# SSFocuser-A-DRV8825.net
KiCad netlist of a schematic drawn in Altium Designer
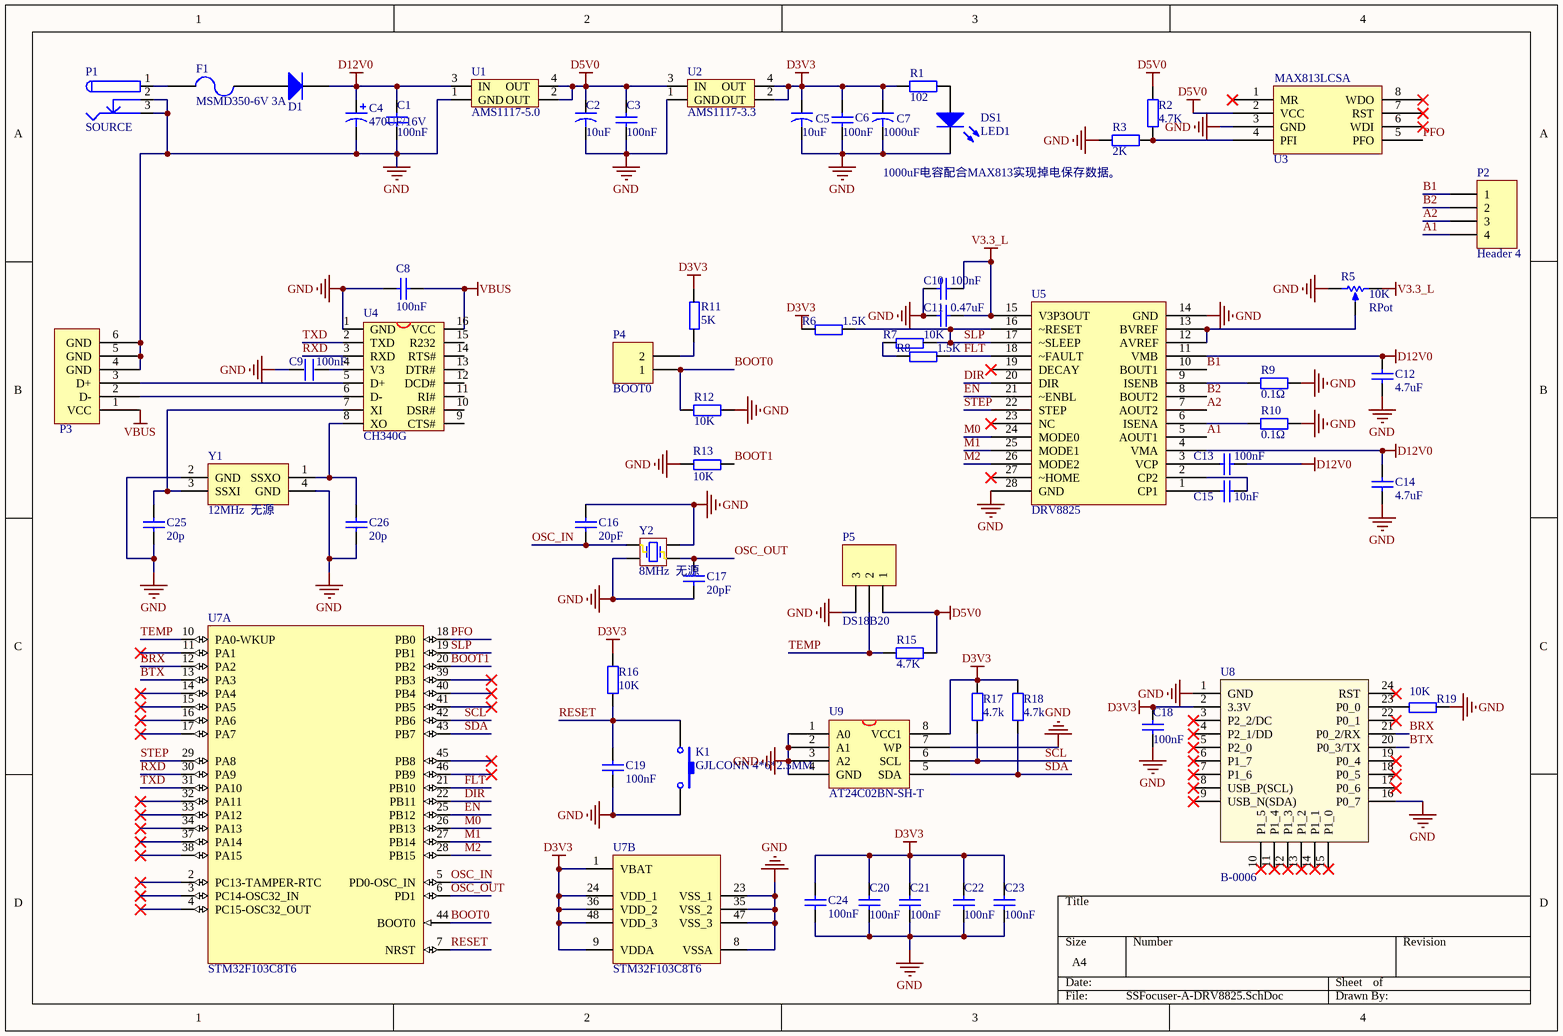
[diagram p0: SSFocuser-A-DRV8825.SchDoc]

(export (version "E")
  (design (tool "Eeschema 10.0.6"))
  (components
    (comp (ref "C1")
      (value "100nF")
      (footprint "0603C")
      (description "Capacitor")
      (fields (field (name "PUBLISHER") "Altium Limited"))
      (libsource (lib "Crazy_PCB") (part "Cap"))
    )
    (comp (ref "C2")
      (value "10uF")
      (footprint "3216")
      (fields (field (name "VAULE") "10uF"))
      (libsource (lib "Crazy_PCB") (part "CAP2"))
    )
    (comp (ref "C3")
      (value "100nF")
      (footprint "0603C")
      (description "Capacitor")
      (fields (field (name "PUBLISHER") "Altium Limited"))
      (libsource (lib "Crazy_PCB") (part "Cap"))
    )
    (comp (ref "C4")
      (value "470UF/16V")
      (footprint "16V/470U(CD10X10D5)")
      (description "470UF      16V      CD10X10D5")
      (libsource (lib "平台原理图symbol图库V1.0") (part "C470UF016S"))
    )
    (comp (ref "C5")
      (value "10uF")
      (footprint "3216")
      (fields (field (name "VAULE") "10uF"))
      (libsource (lib "Crazy_PCB") (part "CAP2"))
    )
    (comp (ref "C6")
      (value "100nF")
      (footprint "0603C")
      (description "Capacitor")
      (fields (field (name "PUBLISHER") "Altium Limited"))
      (libsource (lib "Crazy_PCB") (part "Cap"))
    )
    (comp (ref "C7")
      (value "1000uF")
      (footprint "16V/470U(CD10X10D5)")
      (fields (field (name "VAULE") "1000uF"))
      (libsource (lib "Crazy_PCB") (part "CAP2"))
    )
    (comp (ref "C8")
      (value "100nF")
      (footprint "0603C")
      (description "Capacitor")
      (fields (field (name "PUBLISHER") "Altium Limited"))
      (libsource (lib "Crazy_PCB") (part "Cap"))
    )
    (comp (ref "C9")
      (value "100nF")
      (footprint "0603C")
      (libsource (lib "WarShip V3 STM32103封装库") (part "C"))
    )
    (comp (ref "C10")
      (value "100nF")
      (footprint "0603C")
      (description "Capacitor")
      (fields (field (name "PUBLISHER") "Altium Limited"))
      (libsource (lib "Crazy_PCB") (part "Cap"))
    )
    (comp (ref "C11")
      (value "0.47uF")
      (footprint "0603C")
      (description "Capacitor")
      (fields (field (name "PUBLISHER") "Altium Limited"))
      (libsource (lib "Crazy_PCB") (part "Cap"))
    )
    (comp (ref "C12")
      (value "4.7uF")
      (footprint "1206C")
      (description "Capacitor")
      (fields (field (name "PUBLISHER") "Altium Limited"))
      (libsource (lib "Crazy_PCB") (part "Cap"))
    )
    (comp (ref "C13")
      (value "100nF")
      (footprint "0603C")
      (description "Capacitor")
      (fields (field (name "PUBLISHER") "Altium Limited"))
      (libsource (lib "Crazy_PCB") (part "Cap"))
    )
    (comp (ref "C14")
      (value "4.7uF")
      (footprint "1206C")
      (description "Capacitor")
      (fields (field (name "PUBLISHER") "Altium Limited"))
      (libsource (lib "Crazy_PCB") (part "Cap"))
    )
    (comp (ref "C15")
      (value "10nF")
      (footprint "0603C")
      (description "Capacitor")
      (fields (field (name "PUBLISHER") "Altium Limited"))
      (libsource (lib "Crazy_PCB") (part "Cap"))
    )
    (comp (ref "C16")
      (value "20pF")
      (footprint "0603C")
      (description "Capacitor")
      (fields (field (name "PUBLISHER") "Altium Limited"))
      (libsource (lib "JL_SCH") (part "Cap"))
    )
    (comp (ref "C17")
      (value "20pF")
      (footprint "0603C")
      (description "Capacitor")
      (fields (field (name "PUBLISHER") "Altium Limited"))
      (libsource (lib "JL_SCH") (part "Cap"))
    )
    (comp (ref "C18")
      (value "100nF")
      (footprint "0603C")
      (description "Capacitor")
      (fields (field (name "PUBLISHER") "Altium Limited"))
      (libsource (lib "Crazy_PCB") (part "Cap"))
    )
    (comp (ref "C19")
      (value "100nF")
      (footprint "0603C")
      (description "Capacitor")
      (fields (field (name "PUBLISHER") "Altium Limited"))
      (libsource (lib "Crazy_PCB") (part "Cap"))
    )
    (comp (ref "C20")
      (value "100nF")
      (footprint "0603C")
      (description "Capacitor")
      (fields (field (name "PUBLISHER") "Altium Limited"))
      (libsource (lib "Crazy_PCB") (part "Cap"))
    )
    (comp (ref "C21")
      (value "100nF")
      (footprint "0603C")
      (description "Capacitor")
      (fields (field (name "PUBLISHER") "Altium Limited"))
      (libsource (lib "Crazy_PCB") (part "Cap"))
    )
    (comp (ref "C22")
      (value "100nF")
      (footprint "0603C")
      (description "Capacitor")
      (fields (field (name "PUBLISHER") "Altium Limited"))
      (libsource (lib "Crazy_PCB") (part "Cap"))
    )
    (comp (ref "C23")
      (value "100nF")
      (footprint "0603C")
      (description "Capacitor")
      (fields (field (name "PUBLISHER") "Altium Limited"))
      (libsource (lib "Crazy_PCB") (part "Cap"))
    )
    (comp (ref "C24")
      (value "100nF")
      (footprint "0603C")
      (description "Capacitor")
      (fields (field (name "PUBLISHER") "Altium Limited"))
      (libsource (lib "Crazy_PCB") (part "Cap"))
    )
    (comp (ref "C25")
      (value "20p")
      (footprint "0603C")
      (description "Capacitor")
      (fields (field (name "PUBLISHER") "Altium Limited"))
      (libsource (lib "Crazy_PCB") (part "Cap"))
    )
    (comp (ref "C26")
      (value "20p")
      (footprint "0603C")
      (description "Capacitor")
      (fields (field (name "PUBLISHER") "Altium Limited"))
      (libsource (lib "Crazy_PCB") (part "Cap"))
    )
    (comp (ref "D1")
      (value "M7")
      (footprint "DO-214AC")
      (description "High Conductance Fast Diode")
      (fields (field (name "PUBLISHER") "Altium Limited"))
      (libsource (lib "Crazy_PCB") (part "Diode"))
    )
    (comp (ref "DS1")
      (value "LED1")
      (footprint "0805D")
      (description "Typical RED, GREEN, YELLOW, AMBER GaAs LED")
      (fields (field (name "PUBLISHER") "Altium Limited"))
      (libsource (lib "MiniSTM32 V3.0封装库") (part "LED2"))
    )
    (comp (ref "F1")
      (value "MSMD350-6V 3A")
      (footprint "1812R")
      (description "Fuse")
      (libsource (lib "JL_SCH") (part "FUSE2"))
    )
    (comp (ref "K1")
      (value "GJLCONN 4*6*2.5MM")
      (footprint "SW-4*6")
      (description "Switch")
      (fields (field (name "PUBLISHER") "Altium Limited"))
      (libsource (lib "Crazy_PCB") (part "KEY2"))
    )
    (comp (ref "P1")
      (value "SOURCE")
      (footprint "DC_5.5MM")
      (fields (field (name "PUBLISHER") "Altium Limited"))
      (libsource (lib "Crazy_PCB") (part "SOURCE"))
    )
    (comp (ref "P2")
      (value "Header 4")
      (footprint "XH_4_V")
      (description "Header, 4-Pin")
      (fields (field (name "PUBLISHER") "Altium Limited"))
      (libsource (lib "Miscellaneous Connectors") (part "Header 4"))
    )
    (comp (ref "P3") (value "USB-B") (footprint "USB-B") (libsource (lib "DX") (part "USB-B")))
    (comp (ref "P4")
      (value "BOOT0")
      (footprint "HDR1X2")
      (description "Header, 2-Pin")
      (fields (field (name "PUBLISHER") "Altium Limited"))
      (libsource (lib "Miscellaneous Connectors") (part "MHDR1X2"))
    )
    (comp (ref "P5")
      (value "DS18B20")
      (footprint "TO-92B")
      (description "Header, 3-Pin")
      (fields (field (name "PUBLISHER") "Altium Limited"))
      (libsource (lib "Miscellaneous Connectors") (part "Header 3"))
    )
    (comp (ref "R1")
      (value "102")
      (footprint "0603R")
      (description "Resistor")
      (fields (field (name "PUBLISHER") "Altium Limited"))
      (libsource (lib "") (part "RES_2"))
    )
    (comp (ref "R2")
      (value "4.7K")
      (footprint "0603R")
      (description "Resistor")
      (fields (field (name "PUBLISHER") "Altium Limited"))
      (libsource (lib "") (part "RES_1"))
    )
    (comp (ref "R3")
      (value "2K")
      (footprint "0603R")
      (description "Resistor")
      (fields (field (name "PUBLISHER") "Altium Limited"))
      (libsource (lib "") (part "RES_2"))
    )
    (comp (ref "R5")
      (value "RPot")
      (footprint "VR_SMD")
      (description "Potentiometer")
      (fields (field (name "ALTIUM_VALUE") "10K") (field (name "PUBLISHER") "Altium Limited"))
      (libsource (lib "Miscellaneous Devices") (part "RPot"))
    )
    (comp (ref "R6") (value "1.5K") (footprint "0603R") (libsource (lib "WarShip V3 STM32103封装库") (part "R")))
    (comp (ref "R7") (value "10K") (footprint "0603R") (libsource (lib "WarShip V3 STM32103封装库") (part "R")))
    (comp (ref "R8") (value "1.5K") (footprint "0603R") (libsource (lib "WarShip V3 STM32103封装库") (part "R")))
    (comp (ref "R9")
      (value "0.1Ω")
      (footprint "1206R")
      (description "Resistor")
      (fields (field (name "PUBLISHER") "Altium Limited"))
      (libsource (lib "") (part "RES_2"))
    )
    (comp (ref "R10")
      (value "0.1Ω")
      (footprint "1206R")
      (description "Resistor")
      (fields (field (name "PUBLISHER") "Altium Limited"))
      (libsource (lib "") (part "RES_2"))
    )
    (comp (ref "R11") (value "5K") (footprint "0603R") (libsource (lib "WarShip V3 STM32103封装库") (part "R")))
    (comp (ref "R12")
      (value "10K")
      (footprint "0603R")
      (description "Resistor")
      (fields (field (name "PUBLISHER") "Altium Limited"))
      (libsource (lib "Crazy_PCB") (part "RES"))
    )
    (comp (ref "R13") (value "10K") (footprint "0603R") (libsource (lib "WarShip V3 STM32103封装库") (part "R")))
    (comp (ref "R15")
      (value "4.7K")
      (footprint "0603R")
      (description "Resistor")
      (fields (field (name "PUBLISHER") "Altium Limited"))
      (libsource (lib "Crazy_PCB") (part "RES"))
    )
    (comp (ref "R16")
      (value "10K")
      (footprint "0603R")
      (description "Resistor")
      (fields (field (name "PUBLISHER") "Altium Limited"))
      (libsource (lib "") (part "RES_1"))
    )
    (comp (ref "R17")
      (value "4.7k")
      (footprint "0603R")
      (description "Resistor")
      (fields (field (name "PUBLISHER") "Altium Limited"))
      (libsource (lib "") (part "RES_1"))
    )
    (comp (ref "R18")
      (value "4.7k")
      (footprint "0603R")
      (description "Resistor")
      (fields (field (name "PUBLISHER") "Altium Limited"))
      (libsource (lib "") (part "RES_1"))
    )
    (comp (ref "R19") (value "10K") (footprint "0603R") (libsource (lib "WarShip V3 STM32103封装库") (part "R")))
    (comp (ref "U1")
      (value "AMS1117-5.0")
      (footprint "SOT223")
      (libsource (lib "MiniSTM32 V3.0封装库") (part "AMS1117"))
    )
    (comp (ref "U2")
      (value "AMS1117-3.3")
      (footprint "SOT223")
      (libsource (lib "MiniSTM32 V3.0封装库") (part "AMS1117"))
    )
    (comp (ref "U3") (value "MAX813LCSA") (footprint "SOP-8") (libsource (lib "DX") (part "MAX813L")))
    (comp (ref "U4")
      (value "CH340G")
      (footprint "SO-16")
      (description "USB2UART")
      (libsource (lib "WarShip V3 STM32103封装库") (part "CH340G"))
    )
    (comp (ref "U5") (value "DRV8825") (footprint "HTSSOP") (libsource (lib "MySchlib") (part "DRV8825")))
    (comp (ref "U7")
      (value "STM32F103C8T6")
      (footprint "LQFP48_N")
      (libsource (lib "STMicroelectronics STM32 F1") (part "STM32F103C8T6"))
    )
    (comp (ref "U8") (value "B-0006") (footprint "B-0006") (libsource (lib "B-0006") (part "B-0006")))
    (comp (ref "U9")
      (value "AT24C02BN-SH-T")
      (footprint "SOP-8")
      (libsource (lib "MiniSTM32 V3.0封装库") (part "24C256"))
    )
    (comp (ref "Y1") (value "12MHz  无源") (footprint "X3225") (libsource (lib "JL_SCH") (part "XTAL_3225")))
    (comp (ref "Y2")
      (value "8MHz  无源")
      (footprint "X3225")
      (description "Crystal Oscillator")
      (fields (field (name "PUBLISHER") "Altium Limited"))
      (libsource (lib "JL_SCH") (part "XTAL_1"))
    )
  )
  (nets
    (net (code "1") (name "/A1") (class "Default")
      (node (ref "P2") (pin "4") (pinfunction "4_4") (pintype "passive"))
      (node (ref "U5") (pin "5") (pinfunction "AOUT1_5") (pintype "passive"))
    )
    (net (code "2") (name "/A2") (class "Default")
      (node (ref "P2") (pin "3") (pinfunction "3_3") (pintype "passive"))
      (node (ref "U5") (pin "7") (pinfunction "AOUT2_7") (pintype "passive"))
    )
    (net (code "3") (name "/B1") (class "Default")
      (node (ref "P2") (pin "1") (pinfunction "1_1") (pintype "passive"))
      (node (ref "U5") (pin "10") (pinfunction "BOUT1_10") (pintype "passive"))
    )
    (net (code "4") (name "/B2") (class "Default")
      (node (ref "P2") (pin "2") (pinfunction "2_2") (pintype "passive"))
      (node (ref "U5") (pin "8") (pinfunction "BOUT2_8") (pintype "passive"))
    )
    (net (code "5") (name "/BOOT0") (class "Default")
      (node (ref "P4") (pin "1") (pinfunction "1_1") (pintype "passive"))
      (node (ref "R12") (pin "1") (pinfunction "1_1") (pintype "passive"))
      (node (ref "U7") (pin "44") (pinfunction "BOOT0_44") (pintype "input"))
    )
    (net (code "6") (name "/BOOT1") (class "Default")
      (node (ref "R13") (pin "2") (pintype "passive"))
      (node (ref "U7") (pin "20") (pinfunction "PB2_20") (pintype "bidirectional"))
    )
    (net (code "7") (name "/BRX") (class "Default")
      (node (ref "U7") (pin "12") (pinfunction "PA2_12") (pintype "bidirectional"))
      (node (ref "U8") (pin "21") (pinfunction "P0_2/RX_21") (pintype "passive"))
    )
    (net (code "8") (name "/BTX") (class "Default")
      (node (ref "U7") (pin "13") (pinfunction "PA3_13") (pintype "bidirectional"))
      (node (ref "U8") (pin "20") (pinfunction "P0_3/TX_20") (pintype "passive"))
    )
    (net (code "9") (name "/DIR") (class "Default")
      (node (ref "U5") (pin "20") (pinfunction "DIR_20") (pintype "passive"))
      (node (ref "U7") (pin "22") (pinfunction "PB11_22") (pintype "bidirectional"))
    )
    (net (code "10") (name "/EN") (class "Default")
      (node (ref "U5") (pin "21") (pinfunction "~ENBL_21") (pintype "passive"))
      (node (ref "U7") (pin "25") (pinfunction "PB12_25") (pintype "bidirectional"))
    )
    (net (code "11") (name "/FLT") (class "Default")
      (node (ref "R8") (pin "2") (pintype "passive"))
      (node (ref "U5") (pin "18") (pinfunction "~FAULT_18") (pintype "passive"))
      (node (ref "U7") (pin "21") (pinfunction "PB10_21") (pintype "bidirectional"))
    )
    (net (code "12") (name "/M0") (class "Default")
      (node (ref "U5") (pin "24") (pinfunction "MODE0_24") (pintype "passive"))
      (node (ref "U7") (pin "26") (pinfunction "PB13_26") (pintype "bidirectional"))
    )
    (net (code "13") (name "/M1") (class "Default")
      (node (ref "U5") (pin "25") (pinfunction "MODE1_25") (pintype "passive"))
      (node (ref "U7") (pin "27") (pinfunction "PB14_27") (pintype "bidirectional"))
    )
    (net (code "14") (name "/M2") (class "Default")
      (node (ref "U5") (pin "26") (pinfunction "MODE2_26") (pintype "passive"))
      (node (ref "U7") (pin "28") (pinfunction "PB15_28") (pintype "bidirectional"))
    )
    (net (code "15") (name "/OSC_IN") (class "Default")
      (node (ref "C16") (pin "1") (pinfunction "1_1") (pintype "passive"))
      (node (ref "U7") (pin "5") (pinfunction "PD0-OSC_IN_5") (pintype "bidirectional"))
      (node (ref "Y2") (pin "1") (pinfunction "OSC1_1") (pintype "passive"))
    )
    (net (code "16") (name "/OSC_OUT") (class "Default")
      (node (ref "C17") (pin "1") (pinfunction "1_1") (pintype "passive"))
      (node (ref "U7") (pin "6") (pinfunction "PD1_6") (pintype "bidirectional"))
      (node (ref "Y2") (pin "3") (pinfunction "OSC2_3") (pintype "passive"))
    )
    (net (code "17") (name "/PFO") (class "Default")
      (node (ref "U3") (pin "5") (pinfunction "PFO_5") (pintype "passive"))
      (node (ref "U7") (pin "18") (pinfunction "PB0_18") (pintype "bidirectional"))
    )
    (net (code "18") (name "/RESET") (class "Default")
      (node (ref "C19") (pin "2") (pinfunction "2_2") (pintype "passive"))
      (node (ref "K1") (pin "1") (pinfunction "1_1") (pintype "passive"))
      (node (ref "R16") (pin "1") (pinfunction "1_1") (pintype "passive"))
      (node (ref "U7") (pin "7") (pinfunction "NRST_7") (pintype "bidirectional"))
    )
    (net (code "19") (name "/RXD") (class "Default")
      (node (ref "U4") (pin "3") (pinfunction "RXD_3") (pintype "passive"))
      (node (ref "U7") (pin "30") (pinfunction "PA9_30") (pintype "bidirectional"))
    )
    (net (code "20") (name "/SCL") (class "Default")
      (node (ref "R17") (pin "1") (pinfunction "1_1") (pintype "passive"))
      (node (ref "U7") (pin "42") (pinfunction "PB6_42") (pintype "bidirectional"))
      (node (ref "U9") (pin "6") (pinfunction "SCL_6") (pintype "passive"))
    )
    (net (code "21") (name "/SDA") (class "Default")
      (node (ref "R18") (pin "1") (pinfunction "1_1") (pintype "passive"))
      (node (ref "U7") (pin "43") (pinfunction "PB7_43") (pintype "bidirectional"))
      (node (ref "U9") (pin "5") (pinfunction "SDA_5") (pintype "passive"))
    )
    (net (code "22") (name "/SLP") (class "Default")
      (node (ref "R6") (pin "2") (pintype "passive"))
      (node (ref "R7") (pin "2") (pintype "passive"))
      (node (ref "U5") (pin "16") (pinfunction "~RESET_16") (pintype "passive"))
      (node (ref "U5") (pin "17") (pinfunction "~SLEEP_17") (pintype "passive"))
      (node (ref "U7") (pin "19") (pinfunction "PB1_19") (pintype "bidirectional"))
    )
    (net (code "23") (name "/STEP") (class "Default")
      (node (ref "U5") (pin "22") (pinfunction "STEP_22") (pintype "passive"))
      (node (ref "U7") (pin "29") (pinfunction "PA8_29") (pintype "bidirectional"))
    )
    (net (code "24") (name "/TEMP") (class "Default")
      (node (ref "P5") (pin "2") (pinfunction "2_2") (pintype "passive"))
      (node (ref "R15") (pin "1") (pinfunction "1_1") (pintype "passive"))
      (node (ref "U7") (pin "10") (pinfunction "PA0-WKUP_10") (pintype "bidirectional"))
    )
    (net (code "25") (name "/TXD") (class "Default")
      (node (ref "U4") (pin "2") (pinfunction "TXD_2") (pintype "passive"))
      (node (ref "U7") (pin "31") (pinfunction "PA10_31") (pintype "bidirectional"))
    )
    (net (code "26") (name "D3V3") (class "Default")
      (node (ref "C18") (pin "2") (pinfunction "2_2") (pintype "passive"))
      (node (ref "C20") (pin "2") (pinfunction "2_2") (pintype "passive"))
      (node (ref "C21") (pin "2") (pinfunction "2_2") (pintype "passive"))
      (node (ref "C22") (pin "2") (pinfunction "2_2") (pintype "passive"))
      (node (ref "C23") (pin "2") (pinfunction "2_2") (pintype "passive"))
      (node (ref "C24") (pin "2") (pinfunction "2_2") (pintype "passive"))
      (node (ref "C5") (pin "1") (pinfunction "1_1") (pintype "passive"))
      (node (ref "C6") (pin "2") (pinfunction "2_2") (pintype "passive"))
      (node (ref "C7") (pin "1") (pinfunction "1_1") (pintype "passive"))
      (node (ref "R1") (pin "2") (pinfunction "2_2") (pintype "passive"))
      (node (ref "R11") (pin "2") (pintype "passive"))
      (node (ref "R16") (pin "2") (pinfunction "2_2") (pintype "passive"))
      (node (ref "R17") (pin "2") (pinfunction "2_2") (pintype "passive"))
      (node (ref "R18") (pin "2") (pinfunction "2_2") (pintype "passive"))
      (node (ref "R6") (pin "1") (pintype "passive"))
      (node (ref "U2") (pin "2") (pinfunction "OUT_2") (pintype "passive"))
      (node (ref "U2") (pin "4") (pinfunction "OUT_4") (pintype "passive"))
      (node (ref "U7") (pin "1") (pinfunction "VBAT_1") (pintype "power_in"))
      (node (ref "U7") (pin "24") (pinfunction "VDD_1_24") (pintype "power_in"))
      (node (ref "U7") (pin "36") (pinfunction "VDD_2_36") (pintype "power_in"))
      (node (ref "U7") (pin "48") (pinfunction "VDD_3_48") (pintype "power_in"))
      (node (ref "U7") (pin "9") (pinfunction "VDDA_9") (pintype "power_in"))
      (node (ref "U8") (pin "2") (pinfunction "3.3V_2") (pintype "passive"))
      (node (ref "U9") (pin "8") (pinfunction "VCC1_8") (pintype "passive"))
    )
    (net (code "27") (name "D5V0") (class "Default")
      (node (ref "C2") (pin "1") (pinfunction "1_1") (pintype "passive"))
      (node (ref "C3") (pin "2") (pinfunction "2_2") (pintype "passive"))
      (node (ref "P5") (pin "1") (pinfunction "1_1") (pintype "passive"))
      (node (ref "R15") (pin "2") (pinfunction "2_2") (pintype "passive"))
      (node (ref "R2") (pin "2") (pinfunction "2_2") (pintype "passive"))
      (node (ref "U1") (pin "2") (pinfunction "OUT_2") (pintype "passive"))
      (node (ref "U1") (pin "4") (pinfunction "OUT_4") (pintype "passive"))
      (node (ref "U2") (pin "3") (pinfunction "IN_3") (pintype "passive"))
      (node (ref "U3") (pin "2") (pinfunction "VCC_2") (pintype "passive"))
    )
    (net (code "28") (name "D12V0") (class "Default")
      (node (ref "C1") (pin "2") (pinfunction "2_2") (pintype "passive"))
      (node (ref "C12") (pin "1") (pinfunction "1_1") (pintype "passive"))
      (node (ref "C13") (pin "1") (pinfunction "1_1") (pintype "passive"))
      (node (ref "C14") (pin "1") (pinfunction "1_1") (pintype "passive"))
      (node (ref "C4") (pin "1") (pinfunction "1_1") (pintype "passive"))
      (node (ref "D1") (pin "2") (pinfunction "K_2") (pintype "passive"))
      (node (ref "U1") (pin "3") (pinfunction "IN_3") (pintype "passive"))
      (node (ref "U5") (pin "11") (pinfunction "VMB_11") (pintype "passive"))
      (node (ref "U5") (pin "4") (pinfunction "VMA_4") (pintype "passive"))
    )
    (net (code "29") (name "GND") (class "Default")
      (node (ref "C1") (pin "1") (pinfunction "1_1") (pintype "passive"))
      (node (ref "C10") (pin "1") (pinfunction "1_1") (pintype "passive"))
      (node (ref "C11") (pin "1") (pinfunction "1_1") (pintype "passive"))
      (node (ref "C12") (pin "2") (pinfunction "2_2") (pintype "passive"))
      (node (ref "C14") (pin "2") (pinfunction "2_2") (pintype "passive"))
      (node (ref "C16") (pin "2") (pinfunction "2_2") (pintype "passive"))
      (node (ref "C17") (pin "2") (pinfunction "2_2") (pintype "passive"))
      (node (ref "C18") (pin "1") (pinfunction "1_1") (pintype "passive"))
      (node (ref "C19") (pin "1") (pinfunction "1_1") (pintype "passive"))
      (node (ref "C2") (pin "2") (pinfunction "2_2") (pintype "passive"))
      (node (ref "C20") (pin "1") (pinfunction "1_1") (pintype "passive"))
      (node (ref "C21") (pin "1") (pinfunction "1_1") (pintype "passive"))
      (node (ref "C22") (pin "1") (pinfunction "1_1") (pintype "passive"))
      (node (ref "C23") (pin "1") (pinfunction "1_1") (pintype "passive"))
      (node (ref "C24") (pin "1") (pinfunction "1_1") (pintype "passive"))
      (node (ref "C25") (pin "2") (pinfunction "2_2") (pintype "passive"))
      (node (ref "C26") (pin "2") (pinfunction "2_2") (pintype "passive"))
      (node (ref "C3") (pin "1") (pinfunction "1_1") (pintype "passive"))
      (node (ref "C4") (pin "2") (pinfunction "2_2") (pintype "passive"))
      (node (ref "C5") (pin "2") (pinfunction "2_2") (pintype "passive"))
      (node (ref "C6") (pin "1") (pinfunction "1_1") (pintype "passive"))
      (node (ref "C7") (pin "2") (pinfunction "2_2") (pintype "passive"))
      (node (ref "C8") (pin "1") (pinfunction "1_1") (pintype "passive"))
      (node (ref "C9") (pin "1") (pintype "passive"))
      (node (ref "DS1") (pin "2") (pinfunction "K_2") (pintype "passive"))
      (node (ref "K1") (pin "2") (pinfunction "2_2") (pintype "passive"))
      (node (ref "P1") (pin "2") (pinfunction "2_2") (pintype "power_in"))
      (node (ref "P1") (pin "3") (pinfunction "3_3") (pintype "power_in"))
      (node (ref "P3") (pin "4") (pinfunction "GND_4") (pintype "passive"))
      (node (ref "P3") (pin "5") (pinfunction "GND_5") (pintype "passive"))
      (node (ref "P3") (pin "6") (pinfunction "GND_6") (pintype "passive"))
      (node (ref "P5") (pin "3") (pinfunction "3_3") (pintype "passive"))
      (node (ref "R10") (pin "1") (pinfunction "1_1") (pintype "passive"))
      (node (ref "R12") (pin "2") (pinfunction "2_2") (pintype "passive"))
      (node (ref "R13") (pin "1") (pintype "passive"))
      (node (ref "R19") (pin "2") (pintype "passive"))
      (node (ref "R3") (pin "2") (pinfunction "2_2") (pintype "passive"))
      (node (ref "R5") (pin "1") (pinfunction "TOP_1") (pintype "passive"))
      (node (ref "R9") (pin "1") (pinfunction "1_1") (pintype "passive"))
      (node (ref "U1") (pin "1") (pinfunction "GND_1") (pintype "passive"))
      (node (ref "U2") (pin "1") (pinfunction "GND_1") (pintype "passive"))
      (node (ref "U3") (pin "3") (pinfunction "GND_3") (pintype "passive"))
      (node (ref "U4") (pin "1") (pinfunction "GND_1") (pintype "passive"))
      (node (ref "U5") (pin "14") (pinfunction "GND_14") (pintype "passive"))
      (node (ref "U5") (pin "28") (pinfunction "GND_28") (pintype "passive"))
      (node (ref "U7") (pin "23") (pinfunction "VSS_1_23") (pintype "power_in"))
      (node (ref "U7") (pin "35") (pinfunction "VSS_2_35") (pintype "power_in"))
      (node (ref "U7") (pin "47") (pinfunction "VSS_3_47") (pintype "power_in"))
      (node (ref "U7") (pin "8") (pinfunction "VSSA_8") (pintype "power_in"))
      (node (ref "U8") (pin "1") (pinfunction "GND_1") (pintype "passive"))
      (node (ref "U8") (pin "16") (pinfunction "P0_7_16") (pintype "passive"))
      (node (ref "U9") (pin "1") (pinfunction "A0_1") (pintype "passive"))
      (node (ref "U9") (pin "2") (pinfunction "A1_2") (pintype "passive"))
      (node (ref "U9") (pin "3") (pinfunction "A2_3") (pintype "passive"))
      (node (ref "U9") (pin "4") (pinfunction "GND_4") (pintype "passive"))
      (node (ref "U9") (pin "7") (pinfunction "WP_7") (pintype "passive"))
      (node (ref "Y1") (pin "2") (pinfunction "GND_2") (pintype "passive"))
      (node (ref "Y1") (pin "4") (pinfunction "GND_4") (pintype "passive"))
      (node (ref "Y2") (pin "2") (pinfunction "NA_2") (pintype "passive"))
      (node (ref "Y2") (pin "4") (pinfunction "NA_4") (pintype "passive"))
    )
    (net (code "30") (name "Net-(D1-A)") (class "Default")
      (node (ref "D1") (pin "1") (pinfunction "A_1") (pintype "passive"))
      (node (ref "F1") (pin "1") (pinfunction "1_1") (pintype "passive"))
    )
    (net (code "31") (name "Net-(DS1-A)") (class "Default")
      (node (ref "DS1") (pin "1") (pinfunction "A_1") (pintype "passive"))
      (node (ref "R1") (pin "1") (pinfunction "1_1") (pintype "passive"))
    )
    (net (code "32") (name "Net-(F1-Pad2)") (class "Default")
      (node (ref "F1") (pin "2") (pinfunction "2_2") (pintype "passive"))
      (node (ref "P1") (pin "1") (pinfunction "1_1") (pintype "power_in"))
    )
    (net (code "33") (name "Net-(P3-D+)") (class "Default")
      (node (ref "P3") (pin "3") (pinfunction "D+_3") (pintype "passive"))
      (node (ref "U4") (pin "5") (pinfunction "D+_5") (pintype "passive"))
    )
    (net (code "34") (name "Net-(P3-D-)") (class "Default")
      (node (ref "P3") (pin "2") (pinfunction "D-_2") (pintype "passive"))
      (node (ref "U4") (pin "6") (pinfunction "D-_6") (pintype "passive"))
    )
    (net (code "35") (name "Net-(P4-Pad2)") (class "Default")
      (node (ref "P4") (pin "2") (pinfunction "2_2") (pintype "passive"))
      (node (ref "R11") (pin "1") (pintype "passive"))
    )
    (net (code "36") (name "Net-(R5-TAP)") (class "Default")
      (node (ref "R5") (pin "3") (pinfunction "TAP_3") (pintype "passive"))
      (node (ref "U5") (pin "12") (pinfunction "AVREF_12") (pintype "passive"))
      (node (ref "U5") (pin "13") (pinfunction "BVREF_13") (pintype "passive"))
    )
    (net (code "37") (name "Net-(R7-Pad1)") (class "Default")
      (node (ref "R7") (pin "1") (pintype "passive"))
      (node (ref "R8") (pin "1") (pintype "passive"))
    )
    (net (code "38") (name "Net-(U3-PFI)") (class "Default")
      (node (ref "R2") (pin "1") (pinfunction "1_1") (pintype "passive"))
      (node (ref "R3") (pin "1") (pinfunction "1_1") (pintype "passive"))
      (node (ref "U3") (pin "4") (pinfunction "PFI_4") (pintype "passive"))
    )
    (net (code "39") (name "Net-(U4-V3)") (class "Default")
      (node (ref "C9") (pin "2") (pintype "passive"))
      (node (ref "U4") (pin "4") (pinfunction "V3_4") (pintype "passive"))
    )
    (net (code "40") (name "Net-(U4-XI)") (class "Default")
      (node (ref "C25") (pin "1") (pinfunction "1_1") (pintype "passive"))
      (node (ref "U4") (pin "7") (pinfunction "XI_7") (pintype "passive"))
      (node (ref "Y1") (pin "3") (pinfunction "SSXI_3") (pintype "passive"))
    )
    (net (code "41") (name "Net-(U4-XO)") (class "Default")
      (node (ref "C26") (pin "1") (pinfunction "1_1") (pintype "passive"))
      (node (ref "U4") (pin "8") (pinfunction "XO_8") (pintype "passive"))
      (node (ref "Y1") (pin "1") (pinfunction "SSXO_1") (pintype "passive"))
    )
    (net (code "42") (name "Net-(U5-CP1)") (class "Default")
      (node (ref "C15") (pin "2") (pinfunction "2_2") (pintype "passive"))
      (node (ref "U5") (pin "1") (pinfunction "CP1_1") (pintype "passive"))
    )
    (net (code "43") (name "Net-(U5-CP2)") (class "Default")
      (node (ref "C15") (pin "1") (pinfunction "1_1") (pintype "passive"))
      (node (ref "U5") (pin "2") (pinfunction "CP2_2") (pintype "passive"))
    )
    (net (code "44") (name "Net-(U5-ISENA)") (class "Default")
      (node (ref "R10") (pin "2") (pinfunction "2_2") (pintype "passive"))
      (node (ref "U5") (pin "6") (pinfunction "ISENA_6") (pintype "passive"))
    )
    (net (code "45") (name "Net-(U5-ISENB)") (class "Default")
      (node (ref "R9") (pin "2") (pinfunction "2_2") (pintype "passive"))
      (node (ref "U5") (pin "9") (pinfunction "ISENB_9") (pintype "passive"))
    )
    (net (code "46") (name "Net-(U5-VCP)") (class "Default")
      (node (ref "C13") (pin "2") (pinfunction "2_2") (pintype "passive"))
      (node (ref "U5") (pin "3") (pinfunction "VCP_3") (pintype "passive"))
    )
    (net (code "47") (name "Net-(U8-P0_0)") (class "Default")
      (node (ref "R19") (pin "1") (pintype "passive"))
      (node (ref "U8") (pin "23") (pinfunction "P0_0_23") (pintype "passive"))
    )
    (net (code "48") (name "V3.3_L") (class "Default")
      (node (ref "C10") (pin "2") (pinfunction "2_2") (pintype "passive"))
      (node (ref "C11") (pin "2") (pinfunction "2_2") (pintype "passive"))
      (node (ref "R5") (pin "2") (pinfunction "BOT_2") (pintype "passive"))
      (node (ref "U5") (pin "15") (pinfunction "V3P3OUT_15") (pintype "passive"))
    )
    (net (code "49") (name "VBUS") (class "Default")
      (node (ref "C8") (pin "2") (pinfunction "2_2") (pintype "passive"))
      (node (ref "P3") (pin "1") (pinfunction "VCC_1") (pintype "passive"))
      (node (ref "U4") (pin "16") (pinfunction "VCC_16") (pintype "passive"))
    )
    (net (code "50") (name "unconnected-(U3-MR-Pad1)") (class "Default")
      (node (ref "U3") (pin "1") (pinfunction "MR_1") (pintype "passive+no_connect"))
    )
    (net (code "51") (name "unconnected-(U3-RST-Pad7)") (class "Default")
      (node (ref "U3") (pin "7") (pinfunction "RST_7") (pintype "passive+no_connect"))
    )
    (net (code "52") (name "unconnected-(U3-WDI-Pad6)") (class "Default")
      (node (ref "U3") (pin "6") (pinfunction "WDI_6") (pintype "passive+no_connect"))
    )
    (net (code "53") (name "unconnected-(U3-WDO-Pad8)") (class "Default")
      (node (ref "U3") (pin "8") (pinfunction "WDO_8") (pintype "passive+no_connect"))
    )
    (net (code "54") (name "unconnected-(U4-CTS#-Pad9)") (class "Default")
      (node (ref "U4") (pin "9") (pinfunction "CTS#_9") (pintype "passive"))
    )
    (net (code "55") (name "unconnected-(U4-DCD#-Pad12)") (class "Default")
      (node (ref "U4") (pin "12") (pinfunction "DCD#_12") (pintype "passive"))
    )
    (net (code "56") (name "unconnected-(U4-DSR#-Pad10)") (class "Default")
      (node (ref "U4") (pin "10") (pinfunction "DSR#_10") (pintype "passive"))
    )
    (net (code "57") (name "unconnected-(U4-DTR#-Pad13)") (class "Default")
      (node (ref "U4") (pin "13") (pinfunction "DTR#_13") (pintype "passive"))
    )
    (net (code "58") (name "unconnected-(U4-R232-Pad15)") (class "Default")
      (node (ref "U4") (pin "15") (pinfunction "R232_15") (pintype "passive"))
    )
    (net (code "59") (name "unconnected-(U4-RI#-Pad11)") (class "Default")
      (node (ref "U4") (pin "11") (pinfunction "RI#_11") (pintype "passive"))
    )
    (net (code "60") (name "unconnected-(U4-RTS#-Pad14)") (class "Default")
      (node (ref "U4") (pin "14") (pinfunction "RTS#_14") (pintype "passive"))
    )
    (net (code "61") (name "unconnected-(U5-DECAY-Pad19)") (class "Default")
      (node (ref "U5") (pin "19") (pinfunction "DECAY_19") (pintype "passive+no_connect"))
    )
    (net (code "62") (name "unconnected-(U5-NC-Pad23)") (class "Default")
      (node (ref "U5") (pin "23") (pinfunction "NC_23") (pintype "passive+no_connect"))
    )
    (net (code "63") (name "unconnected-(U5-~HOME-Pad27)") (class "Default")
      (node (ref "U5") (pin "27") (pinfunction "~HOME_27") (pintype "passive+no_connect"))
    )
    (net (code "64") (name "unconnected-(U7A-PA1-Pad11)") (class "Default")
      (node (ref "U7") (pin "11") (pinfunction "PA1_11") (pintype "bidirectional+no_connect"))
    )
    (net (code "65") (name "unconnected-(U7A-PA4-Pad14)") (class "Default")
      (node (ref "U7") (pin "14") (pinfunction "PA4_14") (pintype "bidirectional+no_connect"))
    )
    (net (code "66") (name "unconnected-(U7A-PA5-Pad15)") (class "Default")
      (node (ref "U7") (pin "15") (pinfunction "PA5_15") (pintype "bidirectional+no_connect"))
    )
    (net (code "67") (name "unconnected-(U7A-PA6-Pad16)") (class "Default")
      (node (ref "U7") (pin "16") (pinfunction "PA6_16") (pintype "bidirectional+no_connect"))
    )
    (net (code "68") (name "unconnected-(U7A-PA7-Pad17)") (class "Default")
      (node (ref "U7") (pin "17") (pinfunction "PA7_17") (pintype "bidirectional+no_connect"))
    )
    (net (code "69") (name "unconnected-(U7A-PA11-Pad32)") (class "Default")
      (node (ref "U7") (pin "32") (pinfunction "PA11_32") (pintype "bidirectional+no_connect"))
    )
    (net (code "70") (name "unconnected-(U7A-PA12-Pad33)") (class "Default")
      (node (ref "U7") (pin "33") (pinfunction "PA12_33") (pintype "bidirectional+no_connect"))
    )
    (net (code "71") (name "unconnected-(U7A-PA13-Pad34)") (class "Default")
      (node (ref "U7") (pin "34") (pinfunction "PA13_34") (pintype "bidirectional+no_connect"))
    )
    (net (code "72") (name "unconnected-(U7A-PA14-Pad37)") (class "Default")
      (node (ref "U7") (pin "37") (pinfunction "PA14_37") (pintype "bidirectional+no_connect"))
    )
    (net (code "73") (name "unconnected-(U7A-PA15-Pad38)") (class "Default")
      (node (ref "U7") (pin "38") (pinfunction "PA15_38") (pintype "bidirectional+no_connect"))
    )
    (net (code "74") (name "unconnected-(U7A-PB3-Pad39)") (class "Default")
      (node (ref "U7") (pin "39") (pinfunction "PB3_39") (pintype "bidirectional+no_connect"))
    )
    (net (code "75") (name "unconnected-(U7A-PB4-Pad40)") (class "Default")
      (node (ref "U7") (pin "40") (pinfunction "PB4_40") (pintype "bidirectional+no_connect"))
    )
    (net (code "76") (name "unconnected-(U7A-PB5-Pad41)") (class "Default")
      (node (ref "U7") (pin "41") (pinfunction "PB5_41") (pintype "bidirectional+no_connect"))
    )
    (net (code "77") (name "unconnected-(U7A-PB8-Pad45)") (class "Default")
      (node (ref "U7") (pin "45") (pinfunction "PB8_45") (pintype "bidirectional+no_connect"))
    )
    (net (code "78") (name "unconnected-(U7A-PB9-Pad46)") (class "Default")
      (node (ref "U7") (pin "46") (pinfunction "PB9_46") (pintype "bidirectional+no_connect"))
    )
    (net (code "79") (name "unconnected-(U7A-PC13-TAMPER-RTC-Pad2)") (class "Default")
      (node (ref "U7") (pin "2") (pinfunction "PC13-TAMPER-RTC_2") (pintype "bidirectional+no_connect"))
    )
    (net (code "80") (name "unconnected-(U7A-PC14-OSC32_IN-Pad3)") (class "Default")
      (node (ref "U7") (pin "3") (pinfunction "PC14-OSC32_IN_3") (pintype "bidirectional+no_connect"))
    )
    (net (code "81") (name "unconnected-(U7A-PC15-OSC32_OUT-Pad4)") (class "Default")
      (node (ref "U7") (pin "4") (pinfunction "PC15-OSC32_OUT_4") (pintype "bidirectional+no_connect"))
    )
    (net (code "82") (name "unconnected-(U8-P0_1-Pad22)") (class "Default")
      (node (ref "U8") (pin "22") (pinfunction "P0_1_22") (pintype "passive+no_connect"))
    )
    (net (code "83") (name "unconnected-(U8-P0_4-Pad19)") (class "Default")
      (node (ref "U8") (pin "19") (pinfunction "P0_4_19") (pintype "passive+no_connect"))
    )
    (net (code "84") (name "unconnected-(U8-P0_5-Pad18)") (class "Default")
      (node (ref "U8") (pin "18") (pinfunction "P0_5_18") (pintype "passive+no_connect"))
    )
    (net (code "85") (name "unconnected-(U8-P0_6-Pad17)") (class "Default")
      (node (ref "U8") (pin "17") (pinfunction "P0_6_17") (pintype "passive+no_connect"))
    )
    (net (code "86") (name "unconnected-(U8-P1_0-Pad15)") (class "Default")
      (node (ref "U8") (pin "15") (pinfunction "P1_0_15") (pintype "passive+no_connect"))
    )
    (net (code "87") (name "unconnected-(U8-P1_1-Pad14)") (class "Default")
      (node (ref "U8") (pin "14") (pinfunction "P1_1_14") (pintype "passive+no_connect"))
    )
    (net (code "88") (name "unconnected-(U8-P1_2-Pad13)") (class "Default")
      (node (ref "U8") (pin "13") (pinfunction "P1_2_13") (pintype "passive+no_connect"))
    )
    (net (code "89") (name "unconnected-(U8-P1_3-Pad12)") (class "Default")
      (node (ref "U8") (pin "12") (pinfunction "P1_3_12") (pintype "passive+no_connect"))
    )
    (net (code "90") (name "unconnected-(U8-P1_4-Pad11)") (class "Default")
      (node (ref "U8") (pin "11") (pinfunction "P1_4_11") (pintype "passive+no_connect"))
    )
    (net (code "91") (name "unconnected-(U8-P1_5-Pad10)") (class "Default")
      (node (ref "U8") (pin "10") (pinfunction "P1_5_10") (pintype "passive+no_connect"))
    )
    (net (code "92") (name "unconnected-(U8-P1_6-Pad7)") (class "Default")
      (node (ref "U8") (pin "7") (pinfunction "P1_6_7") (pintype "passive+no_connect"))
    )
    (net (code "93") (name "unconnected-(U8-P1_7-Pad6)") (class "Default")
      (node (ref "U8") (pin "6") (pinfunction "P1_7_6") (pintype "passive+no_connect"))
    )
    (net (code "94") (name "unconnected-(U8-P2_0-Pad5)") (class "Default")
      (node (ref "U8") (pin "5") (pinfunction "P2_0_5") (pintype "passive+no_connect"))
    )
    (net (code "95") (name "unconnected-(U8-P2_1{slash}DD-Pad4)") (class "Default")
      (node (ref "U8") (pin "4") (pinfunction "P2_1/DD_4") (pintype "passive+no_connect"))
    )
    (net (code "96") (name "unconnected-(U8-P2_2{slash}DC-Pad3)") (class "Default")
      (node (ref "U8") (pin "3") (pinfunction "P2_2/DC_3") (pintype "passive+no_connect"))
    )
    (net (code "97") (name "unconnected-(U8-RST-Pad24)") (class "Default")
      (node (ref "U8") (pin "24") (pinfunction "RST_24") (pintype "passive+no_connect"))
    )
    (net (code "98") (name "unconnected-(U8-USB_N(SDA)-Pad9)") (class "Default")
      (node (ref "U8") (pin "9") (pinfunction "USB_N(SDA)_9") (pintype "passive+no_connect"))
    )
    (net (code "99") (name "unconnected-(U8-USB_P(SCL)-Pad8)") (class "Default")
      (node (ref "U8") (pin "8") (pinfunction "USB_P(SCL)_8") (pintype "passive+no_connect"))
    )
  )
)
